# Audio.net
KiCad netlist of a schematic drawn in Altium Designer
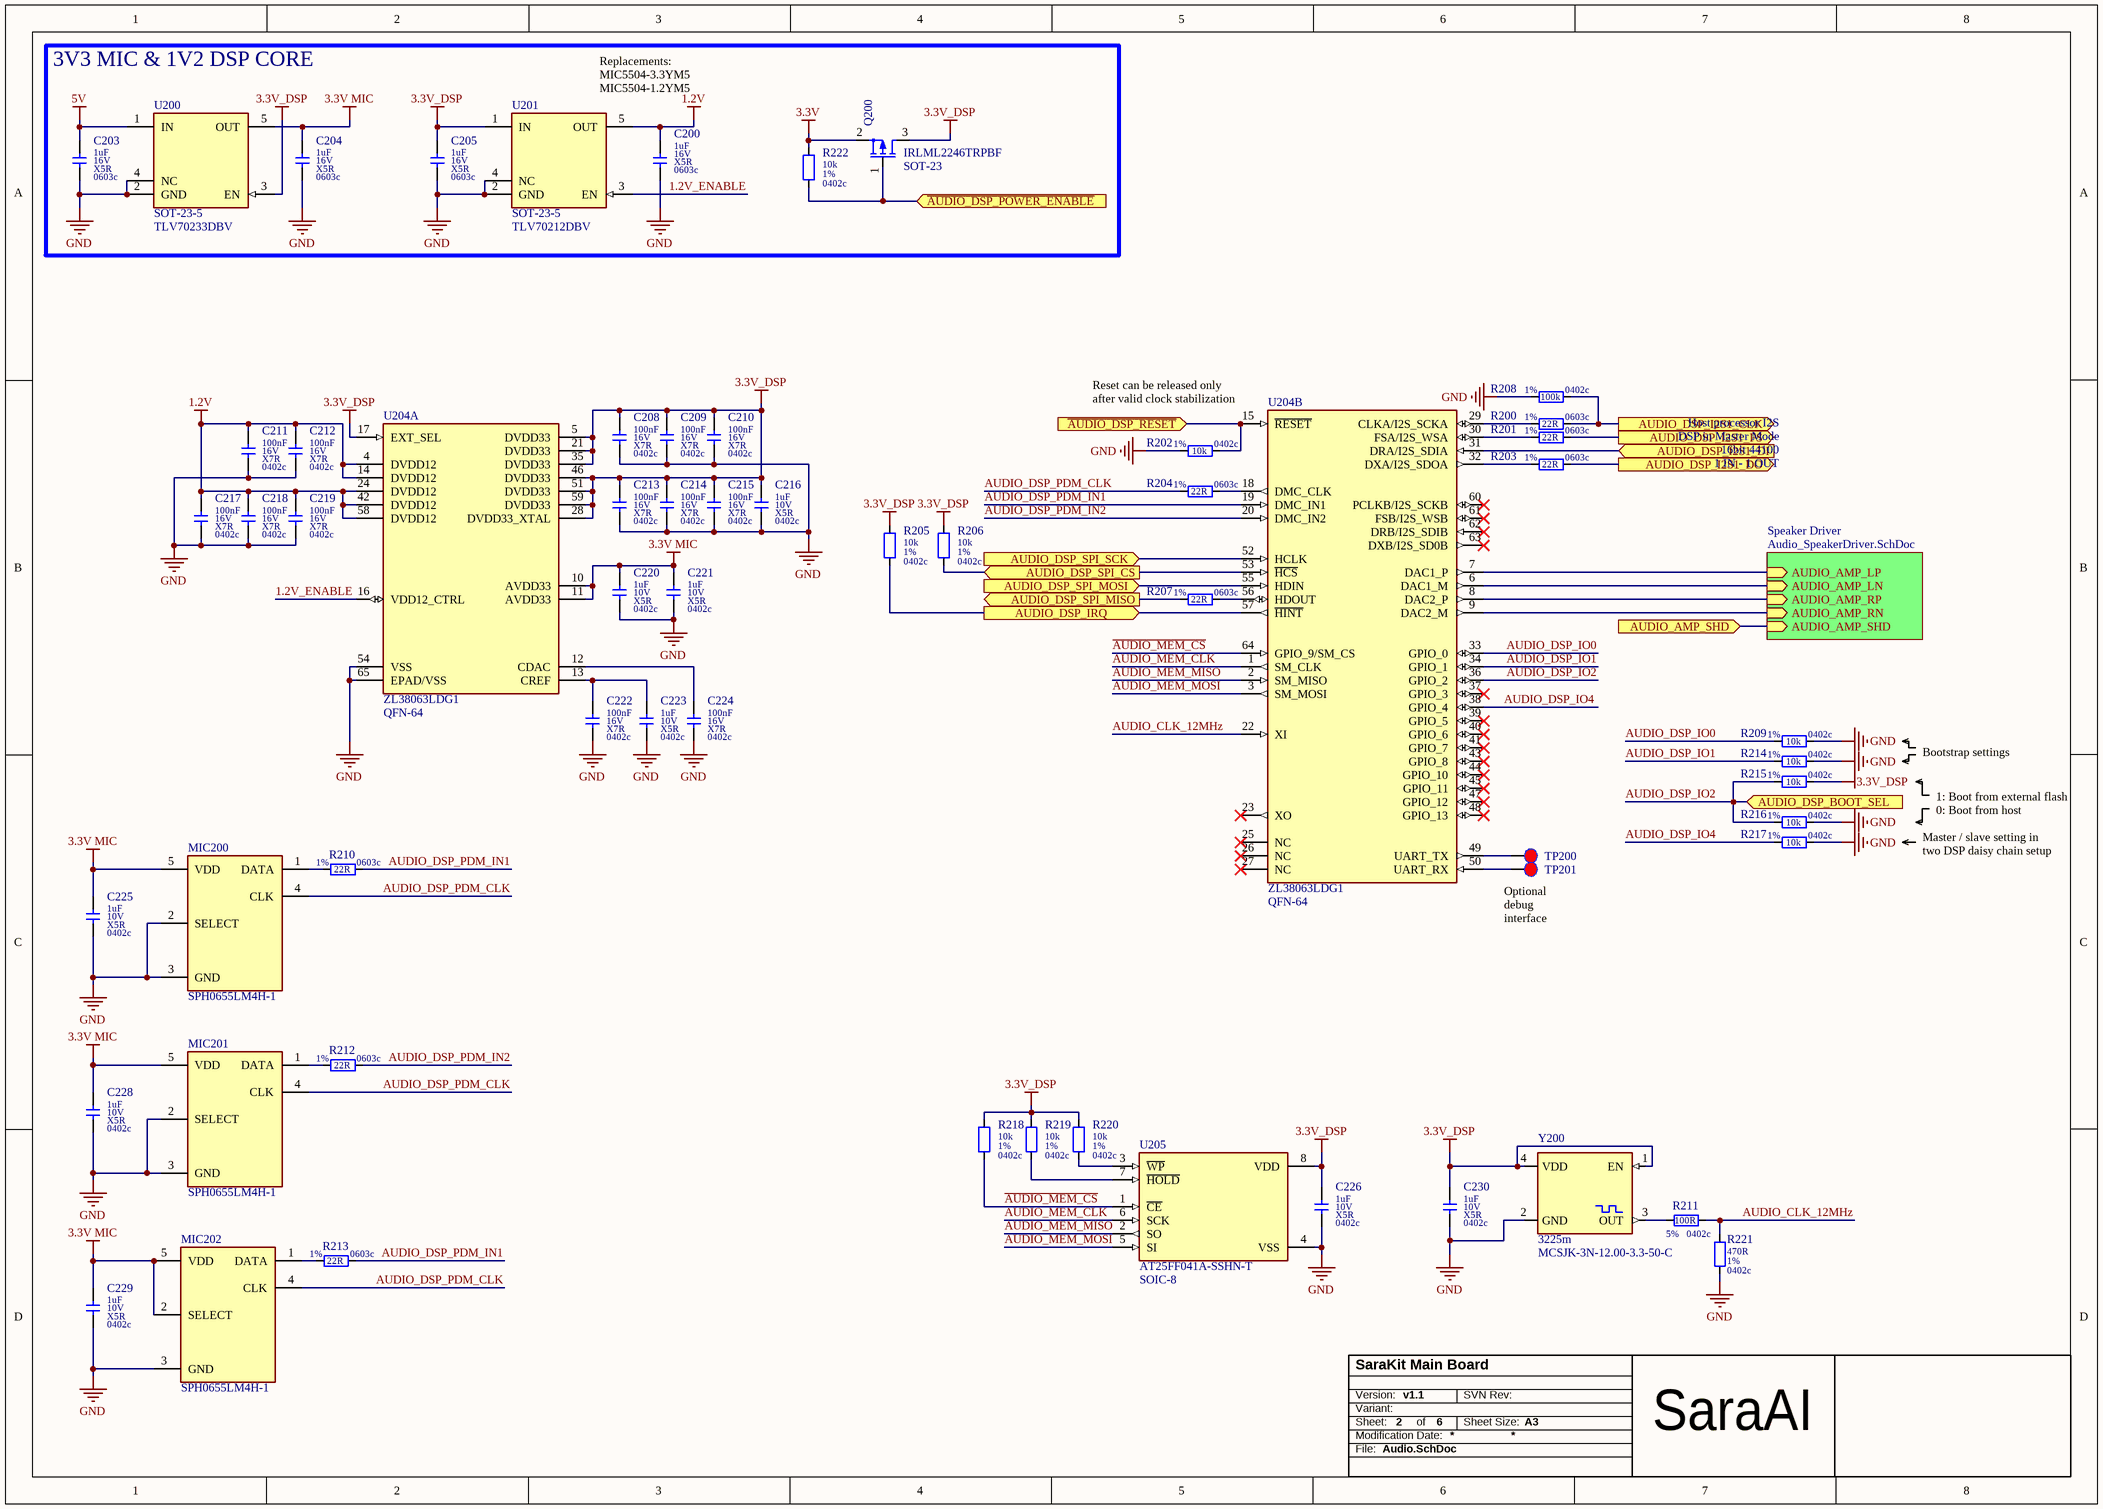
[diagram p0: Audio.SchDoc]

(export (version "E")
  (design (tool "Eeschema 10.0.6"))
  (components
    (comp (ref "C200")
      (value "CL10A105KO8NNNC")
      (footprint "CAPC1608X90L")
      (description "SMT 0603c 1uF 16V 10% X5R 6.9MHz 85'C")
      (fields
        (field (name "11 PARAMETER 4") "X5R")
        (field (name "07 PACKAGE") "0603c")
        (field (name "08 PARAMETER 1") "1uF")
        (field (name "09 PARAMETER 2") "16V")
      )
      (libsource (lib "MS_Altium_Lib") (part "CAPACITOR"))
    )
    (comp (ref "C203")
      (value "CL10A105KO8NNNC")
      (footprint "CAPC1608X90L")
      (description "SMT 0603c 1uF 16V 10% X5R 6.9MHz 85'C")
      (fields
        (field (name "11 PARAMETER 4") "X5R")
        (field (name "07 PACKAGE") "0603c")
        (field (name "08 PARAMETER 1") "1uF")
        (field (name "09 PARAMETER 2") "16V")
      )
      (libsource (lib "MS_Altium_Lib") (part "CAPACITOR"))
    )
    (comp (ref "C204")
      (value "CL10A105KO8NNNC")
      (footprint "CAPC1608X90L")
      (description "SMT 0603c 1uF 16V 10% X5R 6.9MHz 85'C")
      (fields
        (field (name "11 PARAMETER 4") "X5R")
        (field (name "07 PACKAGE") "0603c")
        (field (name "08 PARAMETER 1") "1uF")
        (field (name "09 PARAMETER 2") "16V")
      )
      (libsource (lib "MS_Altium_Lib") (part "CAPACITOR"))
    )
    (comp (ref "C205")
      (value "CL10A105KO8NNNC")
      (footprint "CAPC1608X90L")
      (description "SMT 0603c 1uF 16V 10% X5R 6.9MHz 85'C")
      (fields
        (field (name "11 PARAMETER 4") "X5R")
        (field (name "07 PACKAGE") "0603c")
        (field (name "08 PARAMETER 1") "1uF")
        (field (name "09 PARAMETER 2") "16V")
      )
      (libsource (lib "MS_Altium_Lib") (part "CAPACITOR"))
    )
    (comp (ref "C208")
      (value "CL05B104KO5NNNC")
      (footprint "CAPC1005X60L")
      (description "SMT 0402c 100nF 16V 10% X7R 25.8MHz 125'C")
      (fields
        (field (name "11 PARAMETER 4") "X7R")
        (field (name "07 PACKAGE") "0402c")
        (field (name "08 PARAMETER 1") "100nF")
        (field (name "09 PARAMETER 2") "16V")
      )
      (libsource (lib "MS_Altium_Lib") (part "CAPACITOR"))
    )
    (comp (ref "C209")
      (value "CL05B104KO5NNNC")
      (footprint "CAPC1005X60L")
      (description "SMT 0402c 100nF 16V 10% X7R 25.8MHz 125'C")
      (fields
        (field (name "11 PARAMETER 4") "X7R")
        (field (name "07 PACKAGE") "0402c")
        (field (name "08 PARAMETER 1") "100nF")
        (field (name "09 PARAMETER 2") "16V")
      )
      (libsource (lib "MS_Altium_Lib") (part "CAPACITOR"))
    )
    (comp (ref "C210")
      (value "CL05B104KO5NNNC")
      (footprint "CAPC1005X60L")
      (description "SMT 0402c 100nF 16V 10% X7R 25.8MHz 125'C")
      (fields
        (field (name "11 PARAMETER 4") "X7R")
        (field (name "07 PACKAGE") "0402c")
        (field (name "08 PARAMETER 1") "100nF")
        (field (name "09 PARAMETER 2") "16V")
      )
      (libsource (lib "MS_Altium_Lib") (part "CAPACITOR"))
    )
    (comp (ref "C211")
      (value "CL05B104KO5NNNC")
      (footprint "CAPC1005X60L")
      (description "SMT 0402c 100nF 16V 10% X7R 25.8MHz 125'C")
      (fields
        (field (name "11 PARAMETER 4") "X7R")
        (field (name "07 PACKAGE") "0402c")
        (field (name "08 PARAMETER 1") "100nF")
        (field (name "09 PARAMETER 2") "16V")
      )
      (libsource (lib "MS_Altium_Lib") (part "CAPACITOR"))
    )
    (comp (ref "C212")
      (value "CL05B104KO5NNNC")
      (footprint "CAPC1005X60L")
      (description "SMT 0402c 100nF 16V 10% X7R 25.8MHz 125'C")
      (fields
        (field (name "11 PARAMETER 4") "X7R")
        (field (name "07 PACKAGE") "0402c")
        (field (name "08 PARAMETER 1") "100nF")
        (field (name "09 PARAMETER 2") "16V")
      )
      (libsource (lib "MS_Altium_Lib") (part "CAPACITOR"))
    )
    (comp (ref "C213")
      (value "CL05B104KO5NNNC")
      (footprint "CAPC1005X60L")
      (description "SMT 0402c 100nF 16V 10% X7R 25.8MHz 125'C")
      (fields
        (field (name "11 PARAMETER 4") "X7R")
        (field (name "07 PACKAGE") "0402c")
        (field (name "08 PARAMETER 1") "100nF")
        (field (name "09 PARAMETER 2") "16V")
      )
      (libsource (lib "MS_Altium_Lib") (part "CAPACITOR"))
    )
    (comp (ref "C214")
      (value "CL05B104KO5NNNC")
      (footprint "CAPC1005X60L")
      (description "SMT 0402c 100nF 16V 10% X7R 25.8MHz 125'C")
      (fields
        (field (name "11 PARAMETER 4") "X7R")
        (field (name "07 PACKAGE") "0402c")
        (field (name "08 PARAMETER 1") "100nF")
        (field (name "09 PARAMETER 2") "16V")
      )
      (libsource (lib "MS_Altium_Lib") (part "CAPACITOR"))
    )
    (comp (ref "C215")
      (value "CL05B104KO5NNNC")
      (footprint "CAPC1005X60L")
      (description "SMT 0402c 100nF 16V 10% X7R 25.8MHz 125'C")
      (fields
        (field (name "11 PARAMETER 4") "X7R")
        (field (name "07 PACKAGE") "0402c")
        (field (name "08 PARAMETER 1") "100nF")
        (field (name "09 PARAMETER 2") "16V")
      )
      (libsource (lib "MS_Altium_Lib") (part "CAPACITOR"))
    )
    (comp (ref "C216")
      (value "CL05A105KP5NNNC")
      (footprint "CAPC1005X60L")
      (description "SMT 0402c 1uF 10V 10% X5R 10.2MHz 85'C")
      (fields
        (field (name "11 PARAMETER 4") "X5R")
        (field (name "07 PACKAGE") "0402c")
        (field (name "08 PARAMETER 1") "1uF")
        (field (name "09 PARAMETER 2") "10V")
      )
      (libsource (lib "MS_Altium_Lib") (part "CAPACITOR"))
    )
    (comp (ref "C217")
      (value "CL05B104KO5NNNC")
      (footprint "CAPC1005X60L")
      (description "SMT 0402c 100nF 16V 10% X7R 25.8MHz 125'C")
      (fields
        (field (name "11 PARAMETER 4") "X7R")
        (field (name "07 PACKAGE") "0402c")
        (field (name "08 PARAMETER 1") "100nF")
        (field (name "09 PARAMETER 2") "16V")
      )
      (libsource (lib "MS_Altium_Lib") (part "CAPACITOR"))
    )
    (comp (ref "C218")
      (value "CL05B104KO5NNNC")
      (footprint "CAPC1005X60L")
      (description "SMT 0402c 100nF 16V 10% X7R 25.8MHz 125'C")
      (fields
        (field (name "11 PARAMETER 4") "X7R")
        (field (name "07 PACKAGE") "0402c")
        (field (name "08 PARAMETER 1") "100nF")
        (field (name "09 PARAMETER 2") "16V")
      )
      (libsource (lib "MS_Altium_Lib") (part "CAPACITOR"))
    )
    (comp (ref "C219")
      (value "CL05B104KO5NNNC")
      (footprint "CAPC1005X60L")
      (description "SMT 0402c 100nF 16V 10% X7R 25.8MHz 125'C")
      (fields
        (field (name "11 PARAMETER 4") "X7R")
        (field (name "07 PACKAGE") "0402c")
        (field (name "08 PARAMETER 1") "100nF")
        (field (name "09 PARAMETER 2") "16V")
      )
      (libsource (lib "MS_Altium_Lib") (part "CAPACITOR"))
    )
    (comp (ref "C220")
      (value "CL05A105KP5NNNC")
      (footprint "CAPC1005X60L")
      (description "SMT 0402c 1uF 10V 10% X5R 10.2MHz 85'C")
      (fields
        (field (name "11 PARAMETER 4") "X5R")
        (field (name "07 PACKAGE") "0402c")
        (field (name "08 PARAMETER 1") "1uF")
        (field (name "09 PARAMETER 2") "10V")
      )
      (libsource (lib "MS_Altium_Lib") (part "CAPACITOR"))
    )
    (comp (ref "C221")
      (value "CL05A105KP5NNNC")
      (footprint "CAPC1005X60L")
      (description "SMT 0402c 1uF 10V 10% X5R 10.2MHz 85'C")
      (fields
        (field (name "11 PARAMETER 4") "X5R")
        (field (name "07 PACKAGE") "0402c")
        (field (name "08 PARAMETER 1") "1uF")
        (field (name "09 PARAMETER 2") "10V")
      )
      (libsource (lib "MS_Altium_Lib") (part "CAPACITOR"))
    )
    (comp (ref "C222")
      (value "CL05B104KO5NNNC")
      (footprint "CAPC1005X60L")
      (description "SMT 0402c 100nF 16V 10% X7R 25.8MHz 125'C")
      (fields
        (field (name "11 PARAMETER 4") "X7R")
        (field (name "07 PACKAGE") "0402c")
        (field (name "08 PARAMETER 1") "100nF")
        (field (name "09 PARAMETER 2") "16V")
      )
      (libsource (lib "MS_Altium_Lib") (part "CAPACITOR"))
    )
    (comp (ref "C223")
      (value "CL05A105KP5NNNC")
      (footprint "CAPC1005X60L")
      (description "SMT 0402c 1uF 10V 10% X5R 10.2MHz 85'C")
      (fields
        (field (name "11 PARAMETER 4") "X5R")
        (field (name "07 PACKAGE") "0402c")
        (field (name "08 PARAMETER 1") "1uF")
        (field (name "09 PARAMETER 2") "10V")
      )
      (libsource (lib "MS_Altium_Lib") (part "CAPACITOR"))
    )
    (comp (ref "C224")
      (value "CL05B104KO5NNNC")
      (footprint "CAPC1005X60L")
      (description "SMT 0402c 100nF 16V 10% X7R 25.8MHz 125'C")
      (fields
        (field (name "11 PARAMETER 4") "X7R")
        (field (name "07 PACKAGE") "0402c")
        (field (name "08 PARAMETER 1") "100nF")
        (field (name "09 PARAMETER 2") "16V")
      )
      (libsource (lib "MS_Altium_Lib") (part "CAPACITOR"))
    )
    (comp (ref "C225")
      (value "CL05A105KP5NNNC")
      (footprint "CAPC1005X60L")
      (description "SMT 0402c 1uF 10V 10% X5R 10.2MHz 85'C")
      (fields
        (field (name "11 PARAMETER 4") "X5R")
        (field (name "07 PACKAGE") "0402c")
        (field (name "08 PARAMETER 1") "1uF")
        (field (name "09 PARAMETER 2") "10V")
      )
      (libsource (lib "MS_Altium_Lib") (part "CAPACITOR"))
    )
    (comp (ref "C226")
      (value "CL05A105KP5NNNC")
      (footprint "CAPC1005X60L")
      (description "SMT 0402c 1uF 10V 10% X5R 10.2MHz 85'C")
      (fields
        (field (name "11 PARAMETER 4") "X5R")
        (field (name "07 PACKAGE") "0402c")
        (field (name "08 PARAMETER 1") "1uF")
        (field (name "09 PARAMETER 2") "10V")
      )
      (libsource (lib "MS_Altium_Lib") (part "CAPACITOR"))
    )
    (comp (ref "C228")
      (value "CL05A105KP5NNNC")
      (footprint "CAPC1005X60L")
      (description "SMT 0402c 1uF 10V 10% X5R 10.2MHz 85'C")
      (fields
        (field (name "11 PARAMETER 4") "X5R")
        (field (name "07 PACKAGE") "0402c")
        (field (name "08 PARAMETER 1") "1uF")
        (field (name "09 PARAMETER 2") "10V")
      )
      (libsource (lib "MS_Altium_Lib") (part "CAPACITOR"))
    )
    (comp (ref "C229")
      (value "CL05A105KP5NNNC")
      (footprint "CAPC1005X60L")
      (description "SMT 0402c 1uF 10V 10% X5R 10.2MHz 85'C")
      (fields
        (field (name "11 PARAMETER 4") "X5R")
        (field (name "07 PACKAGE") "0402c")
        (field (name "08 PARAMETER 1") "1uF")
        (field (name "09 PARAMETER 2") "10V")
      )
      (libsource (lib "MS_Altium_Lib") (part "CAPACITOR"))
    )
    (comp (ref "C230")
      (value "CL05A105KP5NNNC")
      (footprint "CAPC1005X60L")
      (description "SMT 0402c 1uF 10V 10% X5R 10.2MHz 85'C")
      (fields
        (field (name "11 PARAMETER 4") "X5R")
        (field (name "07 PACKAGE") "0402c")
        (field (name "08 PARAMETER 1") "1uF")
        (field (name "09 PARAMETER 2") "10V")
      )
      (libsource (lib "MS_Altium_Lib") (part "CAPACITOR"))
    )
    (comp (ref "MIC200")
      (value "SPH0655LM4H-1")
      (footprint "KNOWLES SPH0655LM4H-1")
      (description "SMT -37dBFS 1.65V - 3.6V 25Hz - 22kHz Omnidirectional")
      (fields (field (name "02 MPN") "SPH0655LM4H-1"))
      (libsource (lib "MS_Altium_Lib") (part "SPH0655LM4H-1"))
    )
    (comp (ref "MIC201")
      (value "SPH0655LM4H-1")
      (footprint "KNOWLES SPH0655LM4H-1")
      (description "SMT -37dBFS 1.65V - 3.6V 25Hz - 22kHz Omnidirectional")
      (fields (field (name "02 MPN") "SPH0655LM4H-1"))
      (libsource (lib "MS_Altium_Lib") (part "SPH0655LM4H-1"))
    )
    (comp (ref "MIC202")
      (value "SPH0655LM4H-1")
      (footprint "KNOWLES SPH0655LM4H-1")
      (description "SMT -37dBFS 1.65V - 3.6V 25Hz - 22kHz Omnidirectional")
      (fields (field (name "02 MPN") "SPH0655LM4H-1"))
      (libsource (lib "MS_Altium_Lib") (part "SPH0655LM4H-1"))
    )
    (comp (ref "Q200")
      (value "IRLML2246TRPBF")
      (footprint "SOT95P240X110-3L")
      (description "SMT SOT-23 P-MOS -20V -2.6A 1.3W")
      (fields (field (name "02 MPN") "IRLML2246TRPBF") (field (name "07 PACKAGE") "SOT-23"))
      (libsource (lib "MS_Altium_Lib") (part "TRANSISTOR P-MOSFET 1G 2S 3D"))
    )
    (comp (ref "R200")
      (value "RC0603FR-0722RL")
      (footprint "RESC1608X55L")
      (description "SMT 0603c 22R 1% 100mW 100ppm/K 75V")
      (fields
        (field (name "07 PACKAGE") "0603c")
        (field (name "09 PARAMETER 2") "1%")
        (field (name "08 PARAMETER 1") "22R")
      )
      (libsource (lib "MS_Altium_Lib") (part "RESISTOR"))
    )
    (comp (ref "R201")
      (value "RC0603FR-0722RL")
      (footprint "RESC1608X55L")
      (description "SMT 0603c 22R 1% 100mW 100ppm/K 75V")
      (fields
        (field (name "07 PACKAGE") "0603c")
        (field (name "09 PARAMETER 2") "1%")
        (field (name "08 PARAMETER 1") "22R")
      )
      (libsource (lib "MS_Altium_Lib") (part "RESISTOR"))
    )
    (comp (ref "R202")
      (value "RC0402FR-0710KL")
      (footprint "RESC1005X40L")
      (description "SMT 0402c 10k 1% 62.5mW 100ppm/K 50V")
      (fields
        (field (name "07 PACKAGE") "0402c")
        (field (name "09 PARAMETER 2") "1%")
        (field (name "08 PARAMETER 1") "10k")
      )
      (libsource (lib "MS_Altium_Lib") (part "RESISTOR"))
    )
    (comp (ref "R203")
      (value "RC0603FR-0722RL")
      (footprint "RESC1608X55L")
      (description "SMT 0603c 22R 1% 100mW 100ppm/K 75V")
      (fields
        (field (name "07 PACKAGE") "0603c")
        (field (name "09 PARAMETER 2") "1%")
        (field (name "08 PARAMETER 1") "22R")
      )
      (libsource (lib "MS_Altium_Lib") (part "RESISTOR"))
    )
    (comp (ref "R204")
      (value "RC0603FR-0722RL")
      (footprint "RESC1608X55L")
      (description "SMT 0603c 22R 1% 100mW 100ppm/K 75V")
      (fields
        (field (name "07 PACKAGE") "0603c")
        (field (name "09 PARAMETER 2") "1%")
        (field (name "08 PARAMETER 1") "22R")
      )
      (libsource (lib "MS_Altium_Lib") (part "RESISTOR"))
    )
    (comp (ref "R205")
      (value "RC0402FR-0710KL")
      (footprint "RESC1005X40L")
      (description "SMT 0402c 10k 1% 62.5mW 100ppm/K 50V")
      (fields
        (field (name "07 PACKAGE") "0402c")
        (field (name "09 PARAMETER 2") "1%")
        (field (name "08 PARAMETER 1") "10k")
      )
      (libsource (lib "") (part "RESISTOR_1"))
    )
    (comp (ref "R206")
      (value "RC0402FR-0710KL")
      (footprint "RESC1005X40L")
      (description "SMT 0402c 10k 1% 62.5mW 100ppm/K 50V")
      (fields
        (field (name "07 PACKAGE") "0402c")
        (field (name "09 PARAMETER 2") "1%")
        (field (name "08 PARAMETER 1") "10k")
      )
      (libsource (lib "") (part "RESISTOR_1"))
    )
    (comp (ref "R207")
      (value "RC0603FR-0722RL")
      (footprint "RESC1608X55L")
      (description "SMT 0603c 22R 1% 100mW 100ppm/K 75V")
      (fields
        (field (name "07 PACKAGE") "0603c")
        (field (name "09 PARAMETER 2") "1%")
        (field (name "08 PARAMETER 1") "22R")
      )
      (libsource (lib "MS_Altium_Lib") (part "RESISTOR"))
    )
    (comp (ref "R208")
      (value "RC0402FR-07100KL")
      (footprint "RESC1005X40L")
      (description "SMT 0402c 100k 1% 62.5mW 100ppm/K 50V")
      (fields
        (field (name "07 PACKAGE") "0402c")
        (field (name "09 PARAMETER 2") "1%")
        (field (name "08 PARAMETER 1") "100k")
      )
      (libsource (lib "MS_Altium_Lib") (part "RESISTOR"))
    )
    (comp (ref "R209")
      (value "RC0402FR-0710KL")
      (footprint "RESC1005X40L")
      (description "SMT 0402c 10k 1% 62.5mW 100ppm/K 50V")
      (fields
        (field (name "07 PACKAGE") "0402c")
        (field (name "09 PARAMETER 2") "1%")
        (field (name "08 PARAMETER 1") "10k")
      )
      (libsource (lib "MS_Altium_Lib") (part "RESISTOR"))
    )
    (comp (ref "R210")
      (value "RC0603FR-0722RL")
      (footprint "RESC1608X55L")
      (description "SMT 0603c 22R 1% 100mW 100ppm/K 75V")
      (fields
        (field (name "07 PACKAGE") "0603c")
        (field (name "09 PARAMETER 2") "1%")
        (field (name "08 PARAMETER 1") "22R")
      )
      (libsource (lib "MS_Altium_Lib") (part "RESISTOR"))
    )
    (comp (ref "R211")
      (value "0402WGJ0101TCE")
      (footprint "RESC1005X40L")
      (description "SMT 0402c 100R 5% 62.5mW 200ppm/K 50V")
      (fields
        (field (name "07 PACKAGE") "0402c")
        (field (name "09 PARAMETER 2") "5%")
        (field (name "08 PARAMETER 1") "100R")
      )
      (libsource (lib "MS_Altium_Lib") (part "RESISTOR"))
    )
    (comp (ref "R212")
      (value "RC0603FR-0722RL")
      (footprint "RESC1608X55L")
      (description "SMT 0603c 22R 1% 100mW 100ppm/K 75V")
      (fields
        (field (name "07 PACKAGE") "0603c")
        (field (name "09 PARAMETER 2") "1%")
        (field (name "08 PARAMETER 1") "22R")
      )
      (libsource (lib "MS_Altium_Lib") (part "RESISTOR"))
    )
    (comp (ref "R213")
      (value "RC0603FR-0722RL")
      (footprint "RESC1608X55L")
      (description "SMT 0603c 22R 1% 100mW 100ppm/K 75V")
      (fields
        (field (name "07 PACKAGE") "0603c")
        (field (name "09 PARAMETER 2") "1%")
        (field (name "08 PARAMETER 1") "22R")
      )
      (libsource (lib "MS_Altium_Lib") (part "RESISTOR"))
    )
    (comp (ref "R214")
      (value "RC0402FR-0710KL")
      (footprint "RESC1005X40L")
      (description "SMT 0402c 10k 1% 62.5mW 100ppm/K 50V")
      (fields
        (field (name "07 PACKAGE") "0402c")
        (field (name "09 PARAMETER 2") "1%")
        (field (name "08 PARAMETER 1") "10k")
      )
      (libsource (lib "MS_Altium_Lib") (part "RESISTOR"))
    )
    (comp (ref "R215")
      (value "RC0402FR-0710KL")
      (footprint "RESC1005X40L")
      (description "SMT 0402c 10k 1% 62.5mW 100ppm/K 50V")
      (fields
        (field (name "07 PACKAGE") "0402c")
        (field (name "09 PARAMETER 2") "1%")
        (field (name "08 PARAMETER 1") "10k")
      )
      (libsource (lib "MS_Altium_Lib") (part "RESISTOR"))
    )
    (comp (ref "R216")
      (value "RC0402FR-0710KL")
      (footprint "RESC1005X40L")
      (description "SMT 0402c 10k 1% 62.5mW 100ppm/K 50V")
      (fields
        (field (name "07 PACKAGE") "0402c")
        (field (name "09 PARAMETER 2") "1%")
        (field (name "08 PARAMETER 1") "10k")
      )
      (libsource (lib "MS_Altium_Lib") (part "RESISTOR"))
    )
    (comp (ref "R217")
      (value "RC0402FR-0710KL")
      (footprint "RESC1005X40L")
      (description "SMT 0402c 10k 1% 62.5mW 100ppm/K 50V")
      (fields
        (field (name "07 PACKAGE") "0402c")
        (field (name "09 PARAMETER 2") "1%")
        (field (name "08 PARAMETER 1") "10k")
      )
      (libsource (lib "MS_Altium_Lib") (part "RESISTOR"))
    )
    (comp (ref "R218")
      (value "RC0402FR-0710KL")
      (footprint "RESC1005X40L")
      (description "SMT 0402c 10k 1% 62.5mW 100ppm/K 50V")
      (fields
        (field (name "07 PACKAGE") "0402c")
        (field (name "09 PARAMETER 2") "1%")
        (field (name "08 PARAMETER 1") "10k")
      )
      (libsource (lib "") (part "RESISTOR_1"))
    )
    (comp (ref "R219")
      (value "RC0402FR-0710KL")
      (footprint "RESC1005X40L")
      (description "SMT 0402c 10k 1% 62.5mW 100ppm/K 50V")
      (fields
        (field (name "07 PACKAGE") "0402c")
        (field (name "09 PARAMETER 2") "1%")
        (field (name "08 PARAMETER 1") "10k")
      )
      (libsource (lib "") (part "RESISTOR_1"))
    )
    (comp (ref "R220")
      (value "RC0402FR-0710KL")
      (footprint "RESC1005X40L")
      (description "SMT 0402c 10k 1% 62.5mW 100ppm/K 50V")
      (fields
        (field (name "07 PACKAGE") "0402c")
        (field (name "09 PARAMETER 2") "1%")
        (field (name "08 PARAMETER 1") "10k")
      )
      (libsource (lib "") (part "RESISTOR_1"))
    )
    (comp (ref "R221")
      (value "RC0402FR-07470RL")
      (footprint "RESC1005X40L")
      (description "SMT 0402c 470R 1% 62.5mW 100ppm/K 50V")
      (fields
        (field (name "07 PACKAGE") "0402c")
        (field (name "09 PARAMETER 2") "1%")
        (field (name "08 PARAMETER 1") "470R")
      )
      (libsource (lib "") (part "RESISTOR_1"))
    )
    (comp (ref "R222")
      (value "RC0402FR-0710KL")
      (footprint "RESC1005X40L")
      (description "SMT 0402c 10k 1% 62.5mW 100ppm/K 50V")
      (fields
        (field (name "07 PACKAGE") "0402c")
        (field (name "09 PARAMETER 2") "1%")
        (field (name "08 PARAMETER 1") "10k")
      )
      (libsource (lib "") (part "RESISTOR_1"))
    )
    (comp (ref "TP200")
      (value "TESTPAD")
      (footprint "TP 1.2mm")
      (libsource (lib "MS_Altium_Lib") (part "TESTPAD"))
    )
    (comp (ref "TP201")
      (value "TESTPAD")
      (footprint "TP 1.2mm")
      (libsource (lib "MS_Altium_Lib") (part "TESTPAD"))
    )
    (comp (ref "U200")
      (value "TLV70233DBV")
      (footprint "SOT95P280X145-5L")
      (description "SMT SOT-23-5 3.3V 5.5V 300mA 375mV")
      (fields (field (name "07 PACKAGE") "SOT-23-5") (field (name "02 MPN") "TLV70233DBV"))
      (libsource (lib "MS_Altium_Lib") (part "TLV702_DBV"))
    )
    (comp (ref "U201")
      (value "TLV70212DBV")
      (footprint "SOT95P280X145-5L")
      (description "SMT SOT-23-5 1.2V 5.5V 300mA 375mV")
      (fields (field (name "07 PACKAGE") "SOT-23-5") (field (name "02 MPN") "TLV70212DBV"))
      (libsource (lib "MS_Altium_Lib") (part "TLV702_DBV"))
    )
    (comp (ref "U204")
      (value "ZL38063LDG1")
      (footprint "QFN50P900X900X100_HS-65L")
      (description "SMT QFN-64 Audio DSP and DAC")
      (fields (field (name "02 MPN") "ZL38063LDG1") (field (name "07 PACKAGE") "QFN-64"))
      (libsource (lib "MS_Altium_Lib") (part "ZL38063"))
    )
    (comp (ref "U205")
      (value "AT25FF041A-SSHN-T")
      (footprint "SOIC127P600X175-8L")
      (description "SMT SOIC-8 Flash 4Mbit 1.65V - 3.6V SPI")
      (fields (field (name "02 MPN") "AT25FF041A-SSHN-T") (field (name "07 PACKAGE") "SOIC-8"))
      (libsource (lib "MS_Altium_Lib") (part "SST25VF020B-80-4"))
    )
    (comp (ref "Y200")
      (value "MCSJK-3N-12.00-3.3-50-C")
      (footprint "OSCCC320X250X100L")
      (description "SMT 3225m 12MHz 50ppm")
      (fields (field (name "02 MPN") "MCSJK-3N-12.00-3.3-50-C") (field (name "07 PACKAGE") "3225m"))
      (libsource (lib "MS_Altium_Lib") (part "OSCILLATOR"))
    )
  )
  (nets
    (net (code "1") (name "/1.2V_ENABLE") (class "Default")
      (node (ref "U201") (pin "3") (pinfunction "EN_3") (pintype "input"))
      (node (ref "U204") (pin "16") (pinfunction "VDD12_CTRL_16") (pintype "bidirectional"))
    )
    (net (code "2") (name "/AUDIO_AMP_LN") (class "Default")
      (node (ref "U204") (pin "6") (pinfunction "DAC1_M_6") (pintype "output"))
    )
    (net (code "3") (name "/AUDIO_AMP_LP") (class "Default")
      (node (ref "U204") (pin "7") (pinfunction "DAC1_P_7") (pintype "output"))
    )
    (net (code "4") (name "/AUDIO_AMP_RN") (class "Default")
      (node (ref "U204") (pin "9") (pinfunction "DAC2_M_9") (pintype "output"))
    )
    (net (code "5") (name "/AUDIO_AMP_RP") (class "Default")
      (node (ref "U204") (pin "8") (pinfunction "DAC2_P_8") (pintype "output"))
    )
    (net (code "7") (name "/AUDIO_CLK_12MHz") (class "Default")
      (node (ref "R211") (pin "2") (pinfunction "2_2") (pintype "passive"))
      (node (ref "R221") (pin "2") (pinfunction "2_2") (pintype "passive"))
      (node (ref "U204") (pin "22") (pinfunction "XI_22") (pintype "input"))
    )
    (net (code "8") (name "/AUDIO_DSP_I2S1_CLK") (class "Default")
      (node (ref "R200") (pin "2") (pinfunction "2_2") (pintype "passive"))
      (node (ref "R208") (pin "2") (pinfunction "2_2") (pintype "passive"))
    )
    (net (code "9") (name "/AUDIO_DSP_I2S1_DI") (class "Default")
      (node (ref "U204") (pin "31") (pinfunction "DRA/I2S_SDIA_31") (pintype "input"))
    )
    (net (code "10") (name "/AUDIO_DSP_I2S1_DO") (class "Default")
      (node (ref "R203") (pin "2") (pinfunction "2_2") (pintype "passive"))
    )
    (net (code "11") (name "/AUDIO_DSP_I2S1_FS") (class "Default")
      (node (ref "R201") (pin "2") (pinfunction "2_2") (pintype "passive"))
    )
    (net (code "12") (name "/AUDIO_DSP_IO0") (class "Default")
      (node (ref "R209") (pin "1") (pinfunction "1_1") (pintype "passive"))
      (node (ref "U204") (pin "33") (pinfunction "GPIO_0_33") (pintype "bidirectional"))
    )
    (net (code "13") (name "/AUDIO_DSP_IO1") (class "Default")
      (node (ref "R214") (pin "1") (pinfunction "1_1") (pintype "passive"))
      (node (ref "U204") (pin "34") (pinfunction "GPIO_1_34") (pintype "bidirectional"))
    )
    (net (code "14") (name "/AUDIO_DSP_IO2") (class "Default")
      (node (ref "R215") (pin "1") (pinfunction "1_1") (pintype "passive"))
      (node (ref "R216") (pin "1") (pinfunction "1_1") (pintype "passive"))
      (node (ref "U204") (pin "36") (pinfunction "GPIO_2_36") (pintype "bidirectional"))
    )
    (net (code "15") (name "/AUDIO_DSP_IO4") (class "Default")
      (node (ref "R217") (pin "1") (pinfunction "1_1") (pintype "passive"))
      (node (ref "U204") (pin "38") (pinfunction "GPIO_4_38") (pintype "bidirectional"))
    )
    (net (code "16") (name "/AUDIO_DSP_IRQ") (class "Default")
      (node (ref "R205") (pin "1") (pinfunction "1_1") (pintype "passive"))
      (node (ref "U204") (pin "57") (pinfunction "HINT_57") (pintype "output"))
    )
    (net (code "17") (name "/AUDIO_DSP_PDM_CLK") (class "Default")
      (node (ref "MIC200") (pin "4") (pinfunction "CLK_4") (pintype "passive"))
      (node (ref "MIC201") (pin "4") (pinfunction "CLK_4") (pintype "passive"))
      (node (ref "MIC202") (pin "4") (pinfunction "CLK_4") (pintype "passive"))
      (node (ref "R204") (pin "1") (pinfunction "1_1") (pintype "passive"))
    )
    (net (code "18") (name "/AUDIO_DSP_PDM_IN1") (class "Default")
      (node (ref "R210") (pin "2") (pinfunction "2_2") (pintype "passive"))
      (node (ref "R213") (pin "2") (pinfunction "2_2") (pintype "passive"))
      (node (ref "U204") (pin "19") (pinfunction "DMC_IN1_19") (pintype "input"))
    )
    (net (code "19") (name "/AUDIO_DSP_PDM_IN2") (class "Default")
      (node (ref "R212") (pin "2") (pinfunction "2_2") (pintype "passive"))
      (node (ref "U204") (pin "20") (pinfunction "DMC_IN2_20") (pintype "input"))
    )
    (net (code "20") (name "/AUDIO_DSP_POWER_ENABLE") (class "Default")
      (node (ref "Q200") (pin "1") (pinfunction "G_1") (pintype "passive"))
      (node (ref "R222") (pin "1") (pinfunction "1_1") (pintype "passive"))
    )
    (net (code "21") (name "/AUDIO_DSP_RESET") (class "Default")
      (node (ref "R202") (pin "2") (pinfunction "2_2") (pintype "passive"))
      (node (ref "U204") (pin "15") (pinfunction "RESET_15") (pintype "input"))
    )
    (net (code "22") (name "/AUDIO_DSP_SPI_CS") (class "Default")
      (node (ref "R206") (pin "1") (pinfunction "1_1") (pintype "passive"))
      (node (ref "U204") (pin "53") (pinfunction "HCS_53") (pintype "input"))
    )
    (net (code "23") (name "/AUDIO_DSP_SPI_MISO") (class "Default")
      (node (ref "R207") (pin "1") (pinfunction "1_1") (pintype "passive"))
    )
    (net (code "24") (name "/AUDIO_DSP_SPI_MOSI") (class "Default")
      (node (ref "U204") (pin "55") (pinfunction "HDIN_55") (pintype "input"))
    )
    (net (code "25") (name "/AUDIO_DSP_SPI_SCK") (class "Default")
      (node (ref "U204") (pin "52") (pinfunction "HCLK_52") (pintype "input"))
    )
    (net (code "26") (name "/AUDIO_MEM_CLK") (class "Default")
      (node (ref "U204") (pin "1") (pinfunction "SM_CLK_1") (pintype "output"))
      (node (ref "U205") (pin "6") (pinfunction "SCK_6") (pintype "input"))
    )
    (net (code "27") (name "/AUDIO_MEM_CS") (class "Default")
      (node (ref "R218") (pin "1") (pinfunction "1_1") (pintype "passive"))
      (node (ref "U204") (pin "64") (pinfunction "GPIO_9/SM_CS_64") (pintype "input"))
      (node (ref "U205") (pin "1") (pinfunction "CE_1") (pintype "input"))
    )
    (net (code "28") (name "/AUDIO_MEM_MISO") (class "Default")
      (node (ref "U204") (pin "2") (pinfunction "SM_MISO_2") (pintype "input"))
      (node (ref "U205") (pin "2") (pinfunction "SO_2") (pintype "output"))
    )
    (net (code "29") (name "/AUDIO_MEM_MOSI") (class "Default")
      (node (ref "U204") (pin "3") (pinfunction "SM_MOSI_3") (pintype "output"))
      (node (ref "U205") (pin "5") (pinfunction "SI_5") (pintype "input"))
    )
    (net (code "30") (name "1.2V") (class "Default")
      (node (ref "C200") (pin "2") (pinfunction "2_2") (pintype "passive"))
      (node (ref "C211") (pin "2") (pinfunction "2_2") (pintype "passive"))
      (node (ref "C212") (pin "2") (pinfunction "2_2") (pintype "passive"))
      (node (ref "C217") (pin "2") (pinfunction "2_2") (pintype "passive"))
      (node (ref "C218") (pin "2") (pinfunction "2_2") (pintype "passive"))
      (node (ref "C219") (pin "2") (pinfunction "2_2") (pintype "passive"))
      (node (ref "U201") (pin "5") (pinfunction "OUT_5") (pintype "power_in"))
      (node (ref "U204") (pin "14") (pinfunction "DVDD12_14") (pintype "power_in"))
      (node (ref "U204") (pin "24") (pinfunction "DVDD12_24") (pintype "power_in"))
      (node (ref "U204") (pin "4") (pinfunction "DVDD12_4") (pintype "power_in"))
      (node (ref "U204") (pin "42") (pinfunction "DVDD12_42") (pintype "power_in"))
      (node (ref "U204") (pin "58") (pinfunction "DVDD12_58") (pintype "power_in"))
    )
    (net (code "31") (name "3.3V") (class "Default")
      (node (ref "Q200") (pin "2") (pinfunction "S_2") (pintype "passive"))
      (node (ref "R222") (pin "2") (pinfunction "2_2") (pintype "passive"))
    )
    (net (code "32") (name "3.3V MIC") (class "Default")
      (node (ref "C204") (pin "2") (pinfunction "2_2") (pintype "passive"))
      (node (ref "C220") (pin "2") (pinfunction "2_2") (pintype "passive"))
      (node (ref "C221") (pin "2") (pinfunction "2_2") (pintype "passive"))
      (node (ref "C225") (pin "2") (pinfunction "2_2") (pintype "passive"))
      (node (ref "C228") (pin "2") (pinfunction "2_2") (pintype "passive"))
      (node (ref "C229") (pin "2") (pinfunction "2_2") (pintype "passive"))
      (node (ref "MIC200") (pin "5") (pinfunction "VDD_5") (pintype "passive"))
      (node (ref "MIC201") (pin "5") (pinfunction "VDD_5") (pintype "passive"))
      (node (ref "MIC202") (pin "2") (pinfunction "SELECT_2") (pintype "passive"))
      (node (ref "MIC202") (pin "5") (pinfunction "VDD_5") (pintype "passive"))
      (node (ref "U200") (pin "5") (pinfunction "OUT_5") (pintype "power_in"))
      (node (ref "U204") (pin "10") (pinfunction "AVDD33_10") (pintype "power_in"))
      (node (ref "U204") (pin "11") (pinfunction "AVDD33_11") (pintype "power_in"))
    )
    (net (code "33") (name "3.3V_DSP") (class "Default")
      (node (ref "C205") (pin "2") (pinfunction "2_2") (pintype "passive"))
      (node (ref "C208") (pin "2") (pinfunction "2_2") (pintype "passive"))
      (node (ref "C209") (pin "2") (pinfunction "2_2") (pintype "passive"))
      (node (ref "C210") (pin "2") (pinfunction "2_2") (pintype "passive"))
      (node (ref "C213") (pin "2") (pinfunction "2_2") (pintype "passive"))
      (node (ref "C214") (pin "2") (pinfunction "2_2") (pintype "passive"))
      (node (ref "C215") (pin "2") (pinfunction "2_2") (pintype "passive"))
      (node (ref "C216") (pin "2") (pinfunction "2_2") (pintype "passive"))
      (node (ref "C226") (pin "2") (pinfunction "2_2") (pintype "passive"))
      (node (ref "C230") (pin "2") (pinfunction "2_2") (pintype "passive"))
      (node (ref "Q200") (pin "3") (pinfunction "D_3") (pintype "passive"))
      (node (ref "R205") (pin "2") (pinfunction "2_2") (pintype "passive"))
      (node (ref "R206") (pin "2") (pinfunction "2_2") (pintype "passive"))
      (node (ref "R215") (pin "2") (pinfunction "2_2") (pintype "passive"))
      (node (ref "R218") (pin "2") (pinfunction "2_2") (pintype "passive"))
      (node (ref "R219") (pin "2") (pinfunction "2_2") (pintype "passive"))
      (node (ref "R220") (pin "2") (pinfunction "2_2") (pintype "passive"))
      (node (ref "U200") (pin "3") (pinfunction "EN_3") (pintype "input"))
      (node (ref "U201") (pin "1") (pinfunction "IN_1") (pintype "power_in"))
      (node (ref "U204") (pin "17") (pinfunction "EXT_SEL_17") (pintype "input"))
      (node (ref "U204") (pin "21") (pinfunction "DVDD33_21") (pintype "power_in"))
      (node (ref "U204") (pin "28") (pinfunction "DVDD33_XTAL_28") (pintype "power_in"))
      (node (ref "U204") (pin "35") (pinfunction "DVDD33_35") (pintype "power_in"))
      (node (ref "U204") (pin "46") (pinfunction "DVDD33_46") (pintype "power_in"))
      (node (ref "U204") (pin "5") (pinfunction "DVDD33_5") (pintype "power_in"))
      (node (ref "U204") (pin "51") (pinfunction "DVDD33_51") (pintype "power_in"))
      (node (ref "U204") (pin "59") (pinfunction "DVDD33_59") (pintype "power_in"))
      (node (ref "U205") (pin "8") (pinfunction "VDD_8") (pintype "power_in"))
      (node (ref "Y200") (pin "1") (pinfunction "EN_1") (pintype "input"))
      (node (ref "Y200") (pin "4") (pinfunction "VDD_4") (pintype "power_in"))
    )
    (net (code "34") (name "5V") (class "Default")
      (node (ref "C203") (pin "2") (pinfunction "2_2") (pintype "passive"))
      (node (ref "U200") (pin "1") (pinfunction "IN_1") (pintype "power_in"))
    )
    (net (code "35") (name "GND") (class "Default")
      (node (ref "C200") (pin "1") (pinfunction "1_1") (pintype "passive"))
      (node (ref "C203") (pin "1") (pinfunction "1_1") (pintype "passive"))
      (node (ref "C204") (pin "1") (pinfunction "1_1") (pintype "passive"))
      (node (ref "C205") (pin "1") (pinfunction "1_1") (pintype "passive"))
      (node (ref "C208") (pin "1") (pinfunction "1_1") (pintype "passive"))
      (node (ref "C209") (pin "1") (pinfunction "1_1") (pintype "passive"))
      (node (ref "C210") (pin "1") (pinfunction "1_1") (pintype "passive"))
      (node (ref "C211") (pin "1") (pinfunction "1_1") (pintype "passive"))
      (node (ref "C212") (pin "1") (pinfunction "1_1") (pintype "passive"))
      (node (ref "C213") (pin "1") (pinfunction "1_1") (pintype "passive"))
      (node (ref "C214") (pin "1") (pinfunction "1_1") (pintype "passive"))
      (node (ref "C215") (pin "1") (pinfunction "1_1") (pintype "passive"))
      (node (ref "C216") (pin "1") (pinfunction "1_1") (pintype "passive"))
      (node (ref "C217") (pin "1") (pinfunction "1_1") (pintype "passive"))
      (node (ref "C218") (pin "1") (pinfunction "1_1") (pintype "passive"))
      (node (ref "C219") (pin "1") (pinfunction "1_1") (pintype "passive"))
      (node (ref "C220") (pin "1") (pinfunction "1_1") (pintype "passive"))
      (node (ref "C221") (pin "1") (pinfunction "1_1") (pintype "passive"))
      (node (ref "C222") (pin "1") (pinfunction "1_1") (pintype "passive"))
      (node (ref "C223") (pin "1") (pinfunction "1_1") (pintype "passive"))
      (node (ref "C224") (pin "1") (pinfunction "1_1") (pintype "passive"))
      (node (ref "C225") (pin "1") (pinfunction "1_1") (pintype "passive"))
      (node (ref "C226") (pin "1") (pinfunction "1_1") (pintype "passive"))
      (node (ref "C228") (pin "1") (pinfunction "1_1") (pintype "passive"))
      (node (ref "C229") (pin "1") (pinfunction "1_1") (pintype "passive"))
      (node (ref "C230") (pin "1") (pinfunction "1_1") (pintype "passive"))
      (node (ref "MIC200") (pin "2") (pinfunction "SELECT_2") (pintype "passive"))
      (node (ref "MIC200") (pin "3") (pinfunction "GND_3") (pintype "passive"))
      (node (ref "MIC201") (pin "2") (pinfunction "SELECT_2") (pintype "passive"))
      (node (ref "MIC201") (pin "3") (pinfunction "GND_3") (pintype "passive"))
      (node (ref "MIC202") (pin "3") (pinfunction "GND_3") (pintype "passive"))
      (node (ref "R202") (pin "1") (pinfunction "1_1") (pintype "passive"))
      (node (ref "R208") (pin "1") (pinfunction "1_1") (pintype "passive"))
      (node (ref "R209") (pin "2") (pinfunction "2_2") (pintype "passive"))
      (node (ref "R214") (pin "2") (pinfunction "2_2") (pintype "passive"))
      (node (ref "R216") (pin "2") (pinfunction "2_2") (pintype "passive"))
      (node (ref "R217") (pin "2") (pinfunction "2_2") (pintype "passive"))
      (node (ref "R221") (pin "1") (pinfunction "1_1") (pintype "passive"))
      (node (ref "U200") (pin "2") (pinfunction "GND_2") (pintype "power_in"))
      (node (ref "U200") (pin "4") (pinfunction "NC_4") (pintype "passive"))
      (node (ref "U201") (pin "2") (pinfunction "GND_2") (pintype "power_in"))
      (node (ref "U201") (pin "4") (pinfunction "NC_4") (pintype "passive"))
      (node (ref "U204") (pin "54") (pinfunction "VSS_54") (pintype "power_in"))
      (node (ref "U204") (pin "65") (pinfunction "EPAD/VSS_65") (pintype "power_in"))
      (node (ref "U205") (pin "4") (pinfunction "VSS_4") (pintype "power_in"))
      (node (ref "Y200") (pin "2") (pinfunction "GND_2") (pintype "power_in"))
    )
    (net (code "36") (name "Net-(MIC200-DATA)") (class "Default")
      (node (ref "MIC200") (pin "1") (pinfunction "DATA_1") (pintype "passive"))
      (node (ref "R210") (pin "1") (pinfunction "1_1") (pintype "passive"))
    )
    (net (code "37") (name "Net-(MIC201-DATA)") (class "Default")
      (node (ref "MIC201") (pin "1") (pinfunction "DATA_1") (pintype "passive"))
      (node (ref "R212") (pin "1") (pinfunction "1_1") (pintype "passive"))
    )
    (net (code "38") (name "Net-(MIC202-DATA)") (class "Default")
      (node (ref "MIC202") (pin "1") (pinfunction "DATA_1") (pintype "passive"))
      (node (ref "R213") (pin "1") (pinfunction "1_1") (pintype "passive"))
    )
    (net (code "39") (name "Net-(U204A-CDAC)") (class "Default")
      (node (ref "C224") (pin "2") (pinfunction "2_2") (pintype "passive"))
      (node (ref "U204") (pin "12") (pinfunction "CDAC_12") (pintype "power_in"))
    )
    (net (code "40") (name "Net-(U204A-CREF)") (class "Default")
      (node (ref "C222") (pin "2") (pinfunction "2_2") (pintype "passive"))
      (node (ref "C223") (pin "2") (pinfunction "2_2") (pintype "passive"))
      (node (ref "U204") (pin "13") (pinfunction "CREF_13") (pintype "power_in"))
    )
    (net (code "41") (name "Net-(U204B-CLKA{slash}I2S_SCKA)") (class "Default")
      (node (ref "R200") (pin "1") (pinfunction "1_1") (pintype "passive"))
      (node (ref "U204") (pin "29") (pinfunction "CLKA/I2S_SCKA_29") (pintype "bidirectional"))
    )
    (net (code "42") (name "Net-(U204B-DMC_CLK)") (class "Default")
      (node (ref "R204") (pin "2") (pinfunction "2_2") (pintype "passive"))
      (node (ref "U204") (pin "18") (pinfunction "DMC_CLK_18") (pintype "output"))
    )
    (net (code "43") (name "Net-(U204B-DXA{slash}I2S_SDOA)") (class "Default")
      (node (ref "R203") (pin "1") (pinfunction "1_1") (pintype "passive"))
      (node (ref "U204") (pin "32") (pinfunction "DXA/I2S_SDOA_32") (pintype "output"))
    )
    (net (code "44") (name "Net-(U204B-FSA{slash}I2S_WSA)") (class "Default")
      (node (ref "R201") (pin "1") (pinfunction "1_1") (pintype "passive"))
      (node (ref "U204") (pin "30") (pinfunction "FSA/I2S_WSA_30") (pintype "bidirectional"))
    )
    (net (code "45") (name "Net-(U204B-HDOUT)") (class "Default")
      (node (ref "R207") (pin "2") (pinfunction "2_2") (pintype "passive"))
      (node (ref "U204") (pin "56") (pinfunction "HDOUT_56") (pintype "bidirectional"))
    )
    (net (code "46") (name "Net-(U204B-UART_RX)") (class "Default")
      (node (ref "TP201") (pin "1") (pinfunction "1_1") (pintype "passive"))
      (node (ref "U204") (pin "50") (pinfunction "UART_RX_50") (pintype "input"))
    )
    (net (code "47") (name "Net-(U204B-UART_TX)") (class "Default")
      (node (ref "TP200") (pin "1") (pinfunction "1_1") (pintype "passive"))
      (node (ref "U204") (pin "49") (pinfunction "UART_TX_49") (pintype "output"))
    )
    (net (code "48") (name "Net-(U205-HOLD)") (class "Default")
      (node (ref "R219") (pin "1") (pinfunction "1_1") (pintype "passive"))
      (node (ref "U205") (pin "7") (pinfunction "HOLD_7") (pintype "input"))
    )
    (net (code "49") (name "Net-(U205-WP)") (class "Default")
      (node (ref "R220") (pin "1") (pinfunction "1_1") (pintype "passive"))
      (node (ref "U205") (pin "3") (pinfunction "WP_3") (pintype "input"))
    )
    (net (code "50") (name "Net-(Y200-OUT)") (class "Default")
      (node (ref "R211") (pin "1") (pinfunction "1_1") (pintype "passive"))
      (node (ref "Y200") (pin "3") (pinfunction "OUT_3") (pintype "output"))
    )
    (net (code "51") (name "unconnected-(U204B-DRB{slash}I2S_SDIB-Pad62)") (class "Default")
      (node (ref "U204") (pin "62") (pinfunction "DRB/I2S_SDIB_62") (pintype "input+no_connect"))
    )
    (net (code "52") (name "unconnected-(U204B-DXB{slash}I2S_SD0B-Pad63)") (class "Default")
      (node (ref "U204") (pin "63") (pinfunction "DXB/I2S_SD0B_63") (pintype "output+no_connect"))
    )
    (net (code "53") (name "unconnected-(U204B-FSB{slash}I2S_WSB-Pad61)") (class "Default")
      (node (ref "U204") (pin "61") (pinfunction "FSB/I2S_WSB_61") (pintype "bidirectional+no_connect"))
    )
    (net (code "54") (name "unconnected-(U204B-GPIO_3-Pad37)") (class "Default")
      (node (ref "U204") (pin "37") (pinfunction "GPIO_3_37") (pintype "bidirectional+no_connect"))
    )
    (net (code "55") (name "unconnected-(U204B-GPIO_5-Pad39)") (class "Default")
      (node (ref "U204") (pin "39") (pinfunction "GPIO_5_39") (pintype "bidirectional+no_connect"))
    )
    (net (code "56") (name "unconnected-(U204B-GPIO_6-Pad40)") (class "Default")
      (node (ref "U204") (pin "40") (pinfunction "GPIO_6_40") (pintype "bidirectional+no_connect"))
    )
    (net (code "57") (name "unconnected-(U204B-GPIO_7-Pad41)") (class "Default")
      (node (ref "U204") (pin "41") (pinfunction "GPIO_7_41") (pintype "bidirectional+no_connect"))
    )
    (net (code "58") (name "unconnected-(U204B-GPIO_8-Pad43)") (class "Default")
      (node (ref "U204") (pin "43") (pinfunction "GPIO_8_43") (pintype "bidirectional+no_connect"))
    )
    (net (code "59") (name "unconnected-(U204B-GPIO_10-Pad44)") (class "Default")
      (node (ref "U204") (pin "44") (pinfunction "GPIO_10_44") (pintype "bidirectional+no_connect"))
    )
    (net (code "60") (name "unconnected-(U204B-GPIO_11-Pad45)") (class "Default")
      (node (ref "U204") (pin "45") (pinfunction "GPIO_11_45") (pintype "bidirectional+no_connect"))
    )
    (net (code "61") (name "unconnected-(U204B-GPIO_12-Pad47)") (class "Default")
      (node (ref "U204") (pin "47") (pinfunction "GPIO_12_47") (pintype "bidirectional+no_connect"))
    )
    (net (code "62") (name "unconnected-(U204B-GPIO_13-Pad48)") (class "Default")
      (node (ref "U204") (pin "48") (pinfunction "GPIO_13_48") (pintype "bidirectional+no_connect"))
    )
    (net (code "63") (name "unconnected-(U204B-NC-Pad25)") (class "Default")
      (node (ref "U204") (pin "25") (pinfunction "NC_25") (pintype "passive+no_connect"))
    )
    (net (code "64") (name "unconnected-(U204B-NC-Pad26)") (class "Default")
      (node (ref "U204") (pin "26") (pinfunction "NC_26") (pintype "passive+no_connect"))
    )
    (net (code "65") (name "unconnected-(U204B-NC-Pad27)") (class "Default")
      (node (ref "U204") (pin "27") (pinfunction "NC_27") (pintype "passive+no_connect"))
    )
    (net (code "66") (name "unconnected-(U204B-PCLKB{slash}I2S_SCKB-Pad60)") (class "Default")
      (node (ref "U204") (pin "60") (pinfunction "PCLKB/I2S_SCKB_60") (pintype "bidirectional+no_connect"))
    )
    (net (code "67") (name "unconnected-(U204B-XO-Pad23)") (class "Default")
      (node (ref "U204") (pin "23") (pinfunction "XO_23") (pintype "output+no_connect"))
    )
  )
)
